# V6510_v3.net
KiCad netlist of a schematic drawn in EAGLE
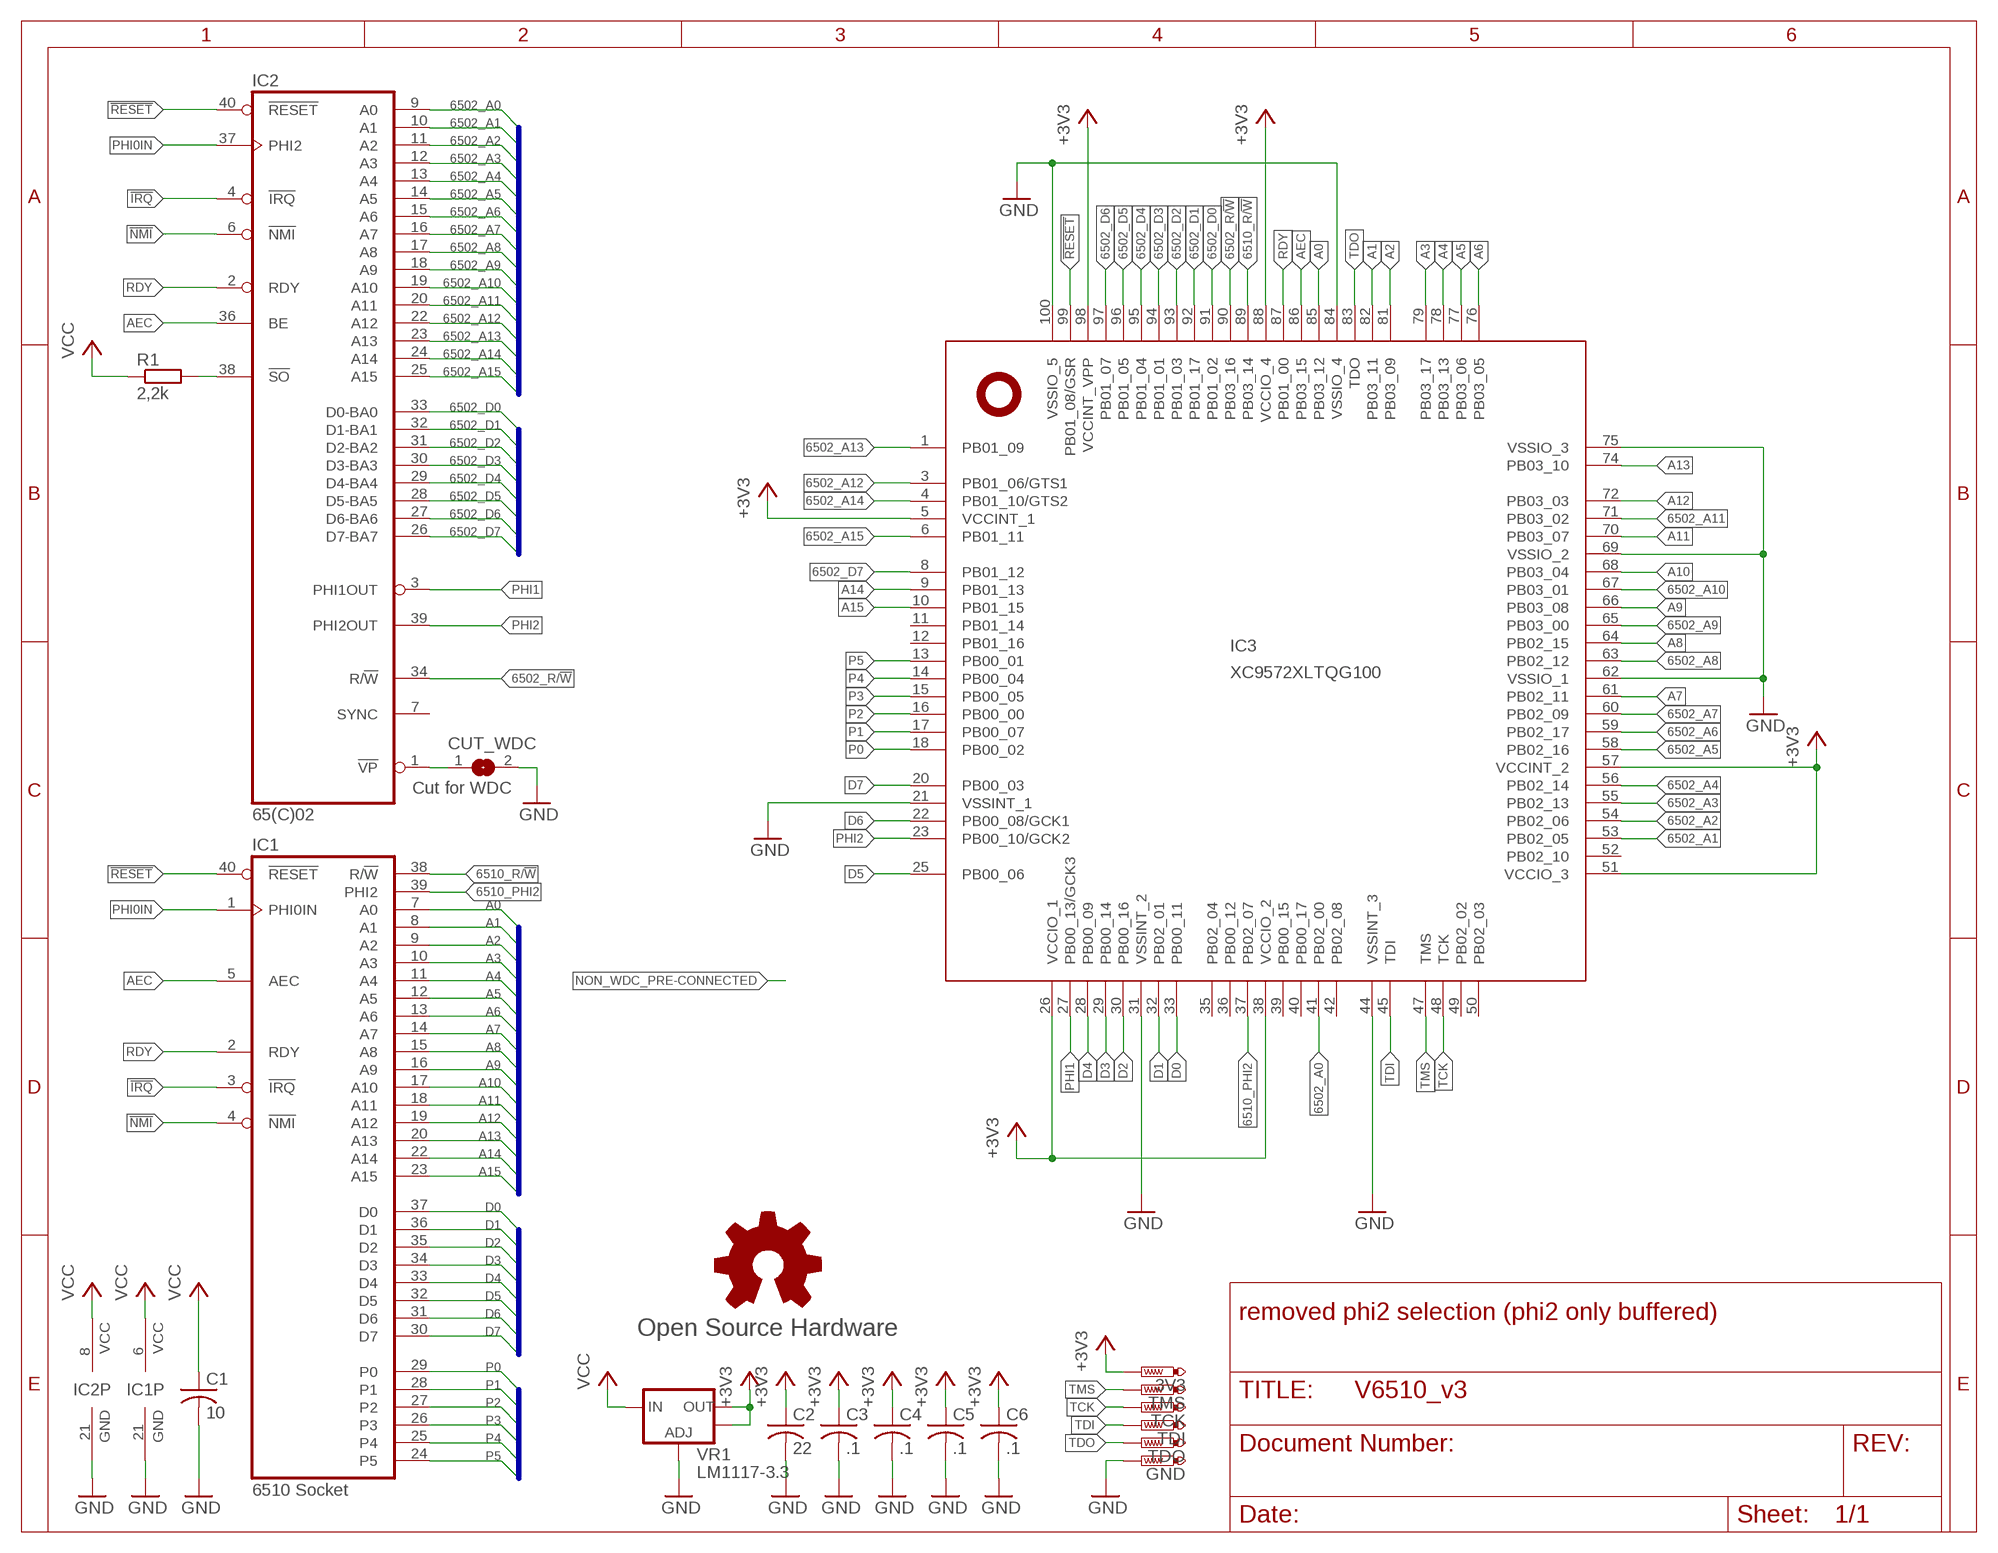
[diagram p0: schematic, sheet 1]

(export (version "E")
  (design (tool "Eeschema 10.0.6"))
  (components
    (comp (ref "3V3")
      (value "PTR1TP08R")
      (footprint "eagle-import:TP08R")
      (libsource (lib "eagle-import") (part "PTR1TP08R"))
    )
    (comp (ref "C1")
      (value "10")
      (footprint "eagle-import:C0805")
      (libsource (lib "eagle-import") (part "C-USC0805"))
    )
    (comp (ref "C2")
      (value "22")
      (footprint "eagle-import:C0805")
      (libsource (lib "eagle-import") (part "C-USC0805"))
    )
    (comp (ref "C3")
      (value ".1")
      (footprint "eagle-import:C0603")
      (libsource (lib "eagle-import") (part "C-USC0603"))
    )
    (comp (ref "C4")
      (value ".1")
      (footprint "eagle-import:C0603")
      (libsource (lib "eagle-import") (part "C-USC0603"))
    )
    (comp (ref "C5")
      (value ".1")
      (footprint "eagle-import:C0603")
      (libsource (lib "eagle-import") (part "C-USC0603"))
    )
    (comp (ref "C6")
      (value ".1")
      (footprint "eagle-import:C0603")
      (libsource (lib "eagle-import") (part "C-USC0603"))
    )
    (comp (ref "CUT_WDC")
      (value "Cut for WDC")
      (footprint "eagle-import:SJ")
      (libsource (lib "eagle-import") (part "SJ"))
    )
    (comp (ref "GND")
      (value "PTR1TP08R")
      (footprint "eagle-import:TP08R")
      (libsource (lib "eagle-import") (part "PTR1TP08R"))
    )
    (comp (ref "GOLD_ORB_SM1")
      (value "Open Source Hardware")
      (footprint "eagle-import:OSHW_5MM")
      (libsource (lib "eagle-import") (part "OSHWLOGOLOGO5MM"))
    )
    (comp (ref "IC1")
      (value "6510 Socket")
      (footprint "eagle-import:DIL40-ROUNDPAD")
      (libsource (lib "eagle-import") (part "6510"))
    )
    (comp (ref "IC2")
      (value "65(C)02")
      (footprint "eagle-import:DIL40-ROUNDPAD")
      (libsource (lib "eagle-import") (part "W65C02S-RP"))
    )
    (comp (ref "IC3")
      (value "XC9572XLTQG100")
      (footprint "eagle-import:TQFP100")
      (libsource (lib "eagle-import") (part "XC9572XLTQG100"))
    )
    (comp (ref "R1")
      (value "2,2k")
      (footprint "eagle-import:0603")
      (libsource (lib "eagle-import") (part "RESISTOR_0603"))
    )
    (comp (ref "TCK")
      (value "PTR1TP08R")
      (footprint "eagle-import:TP08R")
      (libsource (lib "eagle-import") (part "PTR1TP08R"))
    )
    (comp (ref "TDI")
      (value "PTR1TP08R")
      (footprint "eagle-import:TP08R")
      (libsource (lib "eagle-import") (part "PTR1TP08R"))
    )
    (comp (ref "TDO")
      (value "PTR1TP08R")
      (footprint "eagle-import:TP08R")
      (libsource (lib "eagle-import") (part "PTR1TP08R"))
    )
    (comp (ref "TMS")
      (value "PTR1TP08R")
      (footprint "eagle-import:TP08R")
      (libsource (lib "eagle-import") (part "PTR1TP08R"))
    )
    (comp (ref "VR1")
      (value "LM1117-3.3")
      (footprint "eagle-import:SOT223")
      (libsource (lib "eagle-import") (part "V_REG_LM1117SOT223"))
    )
  )
  (nets
    (net (code "1") (name "+3V3") (class "Default")
      (node (ref "3V3") (pin "TP") (pinfunction "TP_TP") (pintype "input"))
      (node (ref "C2") (pin "1") (pinfunction "1_1") (pintype "passive"))
      (node (ref "C3") (pin "1") (pinfunction "1_1") (pintype "passive"))
      (node (ref "C4") (pin "1") (pinfunction "1_1") (pintype "passive"))
      (node (ref "C5") (pin "1") (pinfunction "1_1") (pintype "passive"))
      (node (ref "C6") (pin "1") (pinfunction "1_1") (pintype "passive"))
      (node (ref "IC3") (pin "26") (pinfunction "VCCIO_1_26") (pintype "passive"))
      (node (ref "IC3") (pin "38") (pinfunction "VCCIO_2_38") (pintype "passive"))
      (node (ref "IC3") (pin "5") (pinfunction "VCCINT_1_5") (pintype "passive"))
      (node (ref "IC3") (pin "51") (pinfunction "VCCIO_3_51") (pintype "passive"))
      (node (ref "IC3") (pin "57") (pinfunction "VCCINT_2_57") (pintype "passive"))
      (node (ref "IC3") (pin "88") (pinfunction "VCCIO_4_88") (pintype "passive"))
      (node (ref "IC3") (pin "98") (pinfunction "VCCINT_VPP_98") (pintype "passive"))
      (node (ref "VR1") (pin "2") (pinfunction "OUT_2") (pintype "output"))
      (node (ref "VR1") (pin "4") (pinfunction "OUT_4") (pintype "output"))
    )
    (net (code "2") (name "/6502_R{slash}~{W}") (class "Default")
      (node (ref "IC2") (pin "34") (pinfunction "R/~{W}_34") (pintype "output"))
      (node (ref "IC3") (pin "90") (pinfunction "PB03_16_90") (pintype "bidirectional"))
    )
    (net (code "3") (name "/6510_R{slash}~{W}") (class "Default")
      (node (ref "IC1") (pin "38") (pinfunction "R/~{W}_38") (pintype "output"))
      (node (ref "IC3") (pin "89") (pinfunction "PB03_14_89") (pintype "bidirectional"))
    )
    (net (code "4") (name "/~{IRQ}") (class "Default")
      (node (ref "IC1") (pin "3") (pinfunction "~{IRQ}_3") (pintype "input"))
      (node (ref "IC2") (pin "4") (pinfunction "~{IRQ}_4") (pintype "input"))
    )
    (net (code "5") (name "/~{NMI}") (class "Default")
      (node (ref "IC1") (pin "4") (pinfunction "~{NMI}_4") (pintype "input"))
      (node (ref "IC2") (pin "6") (pinfunction "~{NMI}_6") (pintype "input"))
    )
    (net (code "6") (name "/~{RESET}") (class "Default")
      (node (ref "IC1") (pin "40") (pinfunction "~{RESET}_40") (pintype "input"))
      (node (ref "IC2") (pin "40") (pinfunction "~{RESET}_40") (pintype "input"))
      (node (ref "IC3") (pin "99") (pinfunction "PB01_08/GSR_99") (pintype "bidirectional"))
    )
    (net (code "7") (name "6502_A0") (class "Default")
      (node (ref "IC2") (pin "9") (pinfunction "A0_9") (pintype "tri_state"))
      (node (ref "IC3") (pin "41") (pinfunction "PB02_00_41") (pintype "bidirectional"))
    )
    (net (code "8") (name "6502_A1") (class "Default")
      (node (ref "IC2") (pin "10") (pinfunction "A1_10") (pintype "tri_state"))
      (node (ref "IC3") (pin "53") (pinfunction "PB02_05_53") (pintype "bidirectional"))
    )
    (net (code "9") (name "6502_A2") (class "Default")
      (node (ref "IC2") (pin "11") (pinfunction "A2_11") (pintype "tri_state"))
      (node (ref "IC3") (pin "54") (pinfunction "PB02_06_54") (pintype "bidirectional"))
    )
    (net (code "10") (name "6502_A3") (class "Default")
      (node (ref "IC2") (pin "12") (pinfunction "A3_12") (pintype "tri_state"))
      (node (ref "IC3") (pin "55") (pinfunction "PB02_13_55") (pintype "bidirectional"))
    )
    (net (code "11") (name "6502_A4") (class "Default")
      (node (ref "IC2") (pin "13") (pinfunction "A4_13") (pintype "tri_state"))
      (node (ref "IC3") (pin "56") (pinfunction "PB02_14_56") (pintype "bidirectional"))
    )
    (net (code "12") (name "6502_A5") (class "Default")
      (node (ref "IC2") (pin "14") (pinfunction "A5_14") (pintype "tri_state"))
      (node (ref "IC3") (pin "58") (pinfunction "PB02_16_58") (pintype "bidirectional"))
    )
    (net (code "13") (name "6502_A6") (class "Default")
      (node (ref "IC2") (pin "15") (pinfunction "A6_15") (pintype "tri_state"))
      (node (ref "IC3") (pin "59") (pinfunction "PB02_17_59") (pintype "bidirectional"))
    )
    (net (code "14") (name "6502_A7") (class "Default")
      (node (ref "IC2") (pin "16") (pinfunction "A7_16") (pintype "tri_state"))
      (node (ref "IC3") (pin "60") (pinfunction "PB02_09_60") (pintype "bidirectional"))
    )
    (net (code "15") (name "6502_A8") (class "Default")
      (node (ref "IC2") (pin "17") (pinfunction "A8_17") (pintype "tri_state"))
      (node (ref "IC3") (pin "63") (pinfunction "PB02_12_63") (pintype "bidirectional"))
    )
    (net (code "16") (name "6502_A9") (class "Default")
      (node (ref "IC2") (pin "18") (pinfunction "A9_18") (pintype "tri_state"))
      (node (ref "IC3") (pin "65") (pinfunction "PB03_00_65") (pintype "bidirectional"))
    )
    (net (code "17") (name "6502_A10") (class "Default")
      (node (ref "IC2") (pin "19") (pinfunction "A10_19") (pintype "tri_state"))
      (node (ref "IC3") (pin "67") (pinfunction "PB03_01_67") (pintype "bidirectional"))
    )
    (net (code "18") (name "6502_A11") (class "Default")
      (node (ref "IC2") (pin "20") (pinfunction "A11_20") (pintype "tri_state"))
      (node (ref "IC3") (pin "71") (pinfunction "PB03_02_71") (pintype "bidirectional"))
    )
    (net (code "19") (name "6502_A12") (class "Default")
      (node (ref "IC2") (pin "22") (pinfunction "A12_22") (pintype "tri_state"))
      (node (ref "IC3") (pin "3") (pinfunction "PB01_06/GTS1_3") (pintype "bidirectional"))
    )
    (net (code "20") (name "6502_A13") (class "Default")
      (node (ref "IC2") (pin "23") (pinfunction "A13_23") (pintype "tri_state"))
      (node (ref "IC3") (pin "1") (pinfunction "PB01_09_1") (pintype "bidirectional"))
    )
    (net (code "21") (name "6502_A14") (class "Default")
      (node (ref "IC2") (pin "24") (pinfunction "A14_24") (pintype "tri_state"))
      (node (ref "IC3") (pin "4") (pinfunction "PB01_10/GTS2_4") (pintype "bidirectional"))
    )
    (net (code "22") (name "6502_A15") (class "Default")
      (node (ref "IC2") (pin "25") (pinfunction "A15_25") (pintype "tri_state"))
      (node (ref "IC3") (pin "6") (pinfunction "PB01_11_6") (pintype "bidirectional"))
    )
    (net (code "23") (name "6502_D0") (class "Default")
      (node (ref "IC2") (pin "33") (pinfunction "D0-BA0_33") (pintype "bidirectional"))
      (node (ref "IC3") (pin "91") (pinfunction "PB01_02_91") (pintype "bidirectional"))
    )
    (net (code "24") (name "6502_D1") (class "Default")
      (node (ref "IC2") (pin "32") (pinfunction "D1-BA1_32") (pintype "bidirectional"))
      (node (ref "IC3") (pin "92") (pinfunction "PB01_17_92") (pintype "bidirectional"))
    )
    (net (code "25") (name "6502_D2") (class "Default")
      (node (ref "IC2") (pin "31") (pinfunction "D2-BA2_31") (pintype "bidirectional"))
      (node (ref "IC3") (pin "93") (pinfunction "PB01_03_93") (pintype "bidirectional"))
    )
    (net (code "26") (name "6502_D3") (class "Default")
      (node (ref "IC2") (pin "30") (pinfunction "D3-BA3_30") (pintype "bidirectional"))
      (node (ref "IC3") (pin "94") (pinfunction "PB01_01_94") (pintype "bidirectional"))
    )
    (net (code "27") (name "6502_D4") (class "Default")
      (node (ref "IC2") (pin "29") (pinfunction "D4-BA4_29") (pintype "bidirectional"))
      (node (ref "IC3") (pin "95") (pinfunction "PB01_04_95") (pintype "bidirectional"))
    )
    (net (code "28") (name "6502_D5") (class "Default")
      (node (ref "IC2") (pin "28") (pinfunction "D5-BA5_28") (pintype "bidirectional"))
      (node (ref "IC3") (pin "96") (pinfunction "PB01_05_96") (pintype "bidirectional"))
    )
    (net (code "29") (name "6502_D6") (class "Default")
      (node (ref "IC2") (pin "27") (pinfunction "D6-BA6_27") (pintype "bidirectional"))
      (node (ref "IC3") (pin "97") (pinfunction "PB01_07_97") (pintype "bidirectional"))
    )
    (net (code "30") (name "6502_D7") (class "Default")
      (node (ref "IC2") (pin "26") (pinfunction "D7-BA7_26") (pintype "bidirectional"))
      (node (ref "IC3") (pin "8") (pinfunction "PB01_12_8") (pintype "bidirectional"))
    )
    (net (code "31") (name "6510_PHI2") (class "Default")
      (node (ref "IC1") (pin "39") (pinfunction "PHI2_39") (pintype "output"))
      (node (ref "IC3") (pin "37") (pinfunction "PB02_07_37") (pintype "bidirectional"))
    )
    (net (code "32") (name "A0") (class "Default")
      (node (ref "IC1") (pin "7") (pinfunction "A0_7") (pintype "output"))
      (node (ref "IC3") (pin "85") (pinfunction "PB03_12_85") (pintype "bidirectional"))
    )
    (net (code "33") (name "A1") (class "Default")
      (node (ref "IC1") (pin "8") (pinfunction "A1_8") (pintype "output"))
      (node (ref "IC3") (pin "82") (pinfunction "PB03_11_82") (pintype "bidirectional"))
    )
    (net (code "34") (name "A2") (class "Default")
      (node (ref "IC1") (pin "9") (pinfunction "A2_9") (pintype "output"))
      (node (ref "IC3") (pin "81") (pinfunction "PB03_09_81") (pintype "bidirectional"))
    )
    (net (code "35") (name "A3") (class "Default")
      (node (ref "IC1") (pin "10") (pinfunction "A3_10") (pintype "output"))
      (node (ref "IC3") (pin "79") (pinfunction "PB03_17_79") (pintype "bidirectional"))
    )
    (net (code "36") (name "A4") (class "Default")
      (node (ref "IC1") (pin "11") (pinfunction "A4_11") (pintype "output"))
      (node (ref "IC3") (pin "78") (pinfunction "PB03_13_78") (pintype "bidirectional"))
    )
    (net (code "37") (name "A5") (class "Default")
      (node (ref "IC1") (pin "12") (pinfunction "A5_12") (pintype "output"))
      (node (ref "IC3") (pin "77") (pinfunction "PB03_06_77") (pintype "bidirectional"))
    )
    (net (code "38") (name "A6") (class "Default")
      (node (ref "IC1") (pin "13") (pinfunction "A6_13") (pintype "output"))
      (node (ref "IC3") (pin "76") (pinfunction "PB03_05_76") (pintype "bidirectional"))
    )
    (net (code "39") (name "A7") (class "Default")
      (node (ref "IC1") (pin "14") (pinfunction "A7_14") (pintype "output"))
      (node (ref "IC3") (pin "61") (pinfunction "PB02_11_61") (pintype "bidirectional"))
    )
    (net (code "40") (name "A8") (class "Default")
      (node (ref "IC1") (pin "15") (pinfunction "A8_15") (pintype "output"))
      (node (ref "IC3") (pin "64") (pinfunction "PB02_15_64") (pintype "bidirectional"))
    )
    (net (code "41") (name "A9") (class "Default")
      (node (ref "IC1") (pin "16") (pinfunction "A9_16") (pintype "output"))
      (node (ref "IC3") (pin "66") (pinfunction "PB03_08_66") (pintype "bidirectional"))
    )
    (net (code "42") (name "A10") (class "Default")
      (node (ref "IC1") (pin "17") (pinfunction "A10_17") (pintype "output"))
      (node (ref "IC3") (pin "68") (pinfunction "PB03_04_68") (pintype "bidirectional"))
    )
    (net (code "43") (name "A11") (class "Default")
      (node (ref "IC1") (pin "18") (pinfunction "A11_18") (pintype "output"))
      (node (ref "IC3") (pin "70") (pinfunction "PB03_07_70") (pintype "bidirectional"))
    )
    (net (code "44") (name "A12") (class "Default")
      (node (ref "IC1") (pin "19") (pinfunction "A12_19") (pintype "output"))
      (node (ref "IC3") (pin "72") (pinfunction "PB03_03_72") (pintype "bidirectional"))
    )
    (net (code "45") (name "A13") (class "Default")
      (node (ref "IC1") (pin "20") (pinfunction "A13_20") (pintype "output"))
      (node (ref "IC3") (pin "74") (pinfunction "PB03_10_74") (pintype "bidirectional"))
    )
    (net (code "46") (name "A14") (class "Default")
      (node (ref "IC1") (pin "22") (pinfunction "A14_22") (pintype "output"))
      (node (ref "IC3") (pin "9") (pinfunction "PB01_13_9") (pintype "bidirectional"))
    )
    (net (code "47") (name "A15") (class "Default")
      (node (ref "IC1") (pin "23") (pinfunction "A15_23") (pintype "output"))
      (node (ref "IC3") (pin "10") (pinfunction "PB01_15_10") (pintype "bidirectional"))
    )
    (net (code "48") (name "AEC") (class "Default")
      (node (ref "IC1") (pin "5") (pinfunction "AEC_5") (pintype "input"))
      (node (ref "IC2") (pin "36") (pinfunction "BE_36") (pintype "input"))
      (node (ref "IC3") (pin "86") (pinfunction "PB03_15_86") (pintype "bidirectional"))
    )
    (net (code "49") (name "D0") (class "Default")
      (node (ref "IC1") (pin "37") (pinfunction "D0_37") (pintype "bidirectional"))
      (node (ref "IC3") (pin "33") (pinfunction "PB00_11_33") (pintype "bidirectional"))
    )
    (net (code "50") (name "D1") (class "Default")
      (node (ref "IC1") (pin "36") (pinfunction "D1_36") (pintype "bidirectional"))
      (node (ref "IC3") (pin "32") (pinfunction "PB02_01_32") (pintype "bidirectional"))
    )
    (net (code "51") (name "D2") (class "Default")
      (node (ref "IC1") (pin "35") (pinfunction "D2_35") (pintype "bidirectional"))
      (node (ref "IC3") (pin "30") (pinfunction "PB00_16_30") (pintype "bidirectional"))
    )
    (net (code "52") (name "D3") (class "Default")
      (node (ref "IC1") (pin "34") (pinfunction "D3_34") (pintype "bidirectional"))
      (node (ref "IC3") (pin "29") (pinfunction "PB00_14_29") (pintype "bidirectional"))
    )
    (net (code "53") (name "D4") (class "Default")
      (node (ref "IC1") (pin "33") (pinfunction "D4_33") (pintype "bidirectional"))
      (node (ref "IC3") (pin "28") (pinfunction "PB00_09_28") (pintype "bidirectional"))
    )
    (net (code "54") (name "D5") (class "Default")
      (node (ref "IC1") (pin "32") (pinfunction "D5_32") (pintype "bidirectional"))
      (node (ref "IC3") (pin "25") (pinfunction "PB00_06_25") (pintype "bidirectional"))
    )
    (net (code "55") (name "D6") (class "Default")
      (node (ref "IC1") (pin "31") (pinfunction "D6_31") (pintype "bidirectional"))
      (node (ref "IC3") (pin "22") (pinfunction "PB00_08/GCK1_22") (pintype "bidirectional"))
    )
    (net (code "56") (name "D7") (class "Default")
      (node (ref "IC1") (pin "30") (pinfunction "D7_30") (pintype "bidirectional"))
      (node (ref "IC3") (pin "20") (pinfunction "PB00_03_20") (pintype "bidirectional"))
    )
    (net (code "57") (name "GND") (class "Default")
      (node (ref "C1") (pin "2") (pinfunction "2_2") (pintype "passive"))
      (node (ref "C2") (pin "2") (pinfunction "2_2") (pintype "passive"))
      (node (ref "C3") (pin "2") (pinfunction "2_2") (pintype "passive"))
      (node (ref "C4") (pin "2") (pinfunction "2_2") (pintype "passive"))
      (node (ref "C5") (pin "2") (pinfunction "2_2") (pintype "passive"))
      (node (ref "C6") (pin "2") (pinfunction "2_2") (pintype "passive"))
      (node (ref "CUT_WDC") (pin "2") (pinfunction "2_2") (pintype "passive"))
      (node (ref "GND") (pin "TP") (pinfunction "TP_TP") (pintype "input"))
      (node (ref "IC1") (pin "21") (pinfunction "GND_21") (pintype "power_in"))
      (node (ref "IC2") (pin "21") (pinfunction "GND_21") (pintype "power_in"))
      (node (ref "IC3") (pin "100") (pinfunction "VSSIO_5_100") (pintype "passive"))
      (node (ref "IC3") (pin "21") (pinfunction "VSSINT_1_21") (pintype "passive"))
      (node (ref "IC3") (pin "31") (pinfunction "VSSINT_2_31") (pintype "passive"))
      (node (ref "IC3") (pin "44") (pinfunction "VSSINT_3_44") (pintype "passive"))
      (node (ref "IC3") (pin "62") (pinfunction "VSSIO_1_62") (pintype "passive"))
      (node (ref "IC3") (pin "69") (pinfunction "VSSIO_2_69") (pintype "passive"))
      (node (ref "IC3") (pin "75") (pinfunction "VSSIO_3_75") (pintype "passive"))
      (node (ref "IC3") (pin "84") (pinfunction "VSSIO_4_84") (pintype "passive"))
      (node (ref "VR1") (pin "1") (pinfunction "ADJ_1") (pintype "input"))
    )
    (net (code "59") (name "Net-(IC2A-~{SO})") (class "Default")
      (node (ref "IC2") (pin "38") (pinfunction "~{SO}_38") (pintype "output"))
      (node (ref "R1") (pin "2") (pinfunction "2_2") (pintype "passive"))
    )
    (net (code "60") (name "Net-(IC2A-~{VP})") (class "Default")
      (node (ref "CUT_WDC") (pin "1") (pinfunction "1_1") (pintype "passive"))
      (node (ref "IC2") (pin "1") (pinfunction "~{VP}_1") (pintype "output"))
    )
    (net (code "61") (name "P0") (class "Default")
      (node (ref "IC1") (pin "29") (pinfunction "P0_29") (pintype "output"))
      (node (ref "IC3") (pin "18") (pinfunction "PB00_02_18") (pintype "bidirectional"))
    )
    (net (code "62") (name "P1") (class "Default")
      (node (ref "IC1") (pin "28") (pinfunction "P1_28") (pintype "output"))
      (node (ref "IC3") (pin "17") (pinfunction "PB00_07_17") (pintype "bidirectional"))
    )
    (net (code "63") (name "P2") (class "Default")
      (node (ref "IC1") (pin "27") (pinfunction "P2_27") (pintype "output"))
      (node (ref "IC3") (pin "16") (pinfunction "PB00_00_16") (pintype "bidirectional"))
    )
    (net (code "64") (name "P3") (class "Default")
      (node (ref "IC1") (pin "26") (pinfunction "P3_26") (pintype "output"))
      (node (ref "IC3") (pin "15") (pinfunction "PB00_05_15") (pintype "bidirectional"))
    )
    (net (code "65") (name "P4") (class "Default")
      (node (ref "IC1") (pin "25") (pinfunction "P4_25") (pintype "output"))
      (node (ref "IC3") (pin "14") (pinfunction "PB00_04_14") (pintype "bidirectional"))
    )
    (net (code "66") (name "P5") (class "Default")
      (node (ref "IC1") (pin "24") (pinfunction "P5_24") (pintype "output"))
      (node (ref "IC3") (pin "13") (pinfunction "PB00_01_13") (pintype "bidirectional"))
    )
    (net (code "67") (name "PHI0IN") (class "Default")
      (node (ref "IC1") (pin "1") (pinfunction "PHI0IN_1") (pintype "input"))
      (node (ref "IC2") (pin "37") (pinfunction "PHI2_37") (pintype "input"))
    )
    (net (code "68") (name "PHI1") (class "Default")
      (node (ref "IC2") (pin "3") (pinfunction "PHI1OUT_3") (pintype "input"))
      (node (ref "IC3") (pin "27") (pinfunction "PB00_13/GCK3_27") (pintype "bidirectional"))
    )
    (net (code "69") (name "PHI2") (class "Default")
      (node (ref "IC2") (pin "39") (pinfunction "PHI2OUT_39") (pintype "output"))
      (node (ref "IC3") (pin "23") (pinfunction "PB00_10/GCK2_23") (pintype "bidirectional"))
    )
    (net (code "70") (name "RDY") (class "Default")
      (node (ref "IC1") (pin "2") (pinfunction "RDY_2") (pintype "input"))
      (node (ref "IC2") (pin "2") (pinfunction "RDY_2") (pintype "bidirectional"))
      (node (ref "IC3") (pin "87") (pinfunction "PB01_00_87") (pintype "bidirectional"))
    )
    (net (code "71") (name "TCK") (class "Default")
      (node (ref "IC3") (pin "48") (pinfunction "TCK_48") (pintype "input"))
      (node (ref "TCK") (pin "TP") (pinfunction "TP_TP") (pintype "input"))
    )
    (net (code "72") (name "TDI") (class "Default")
      (node (ref "IC3") (pin "45") (pinfunction "TDI_45") (pintype "input"))
      (node (ref "TDI") (pin "TP") (pinfunction "TP_TP") (pintype "input"))
    )
    (net (code "73") (name "TDO") (class "Default")
      (node (ref "IC3") (pin "83") (pinfunction "TDO_83") (pintype "output"))
      (node (ref "TDO") (pin "TP") (pinfunction "TP_TP") (pintype "input"))
    )
    (net (code "74") (name "TMS") (class "Default")
      (node (ref "IC3") (pin "47") (pinfunction "TMS_47") (pintype "input"))
      (node (ref "TMS") (pin "TP") (pinfunction "TP_TP") (pintype "input"))
    )
    (net (code "75") (name "VCC") (class "Default")
      (node (ref "C1") (pin "1") (pinfunction "1_1") (pintype "passive"))
      (node (ref "IC1") (pin "6") (pinfunction "VCC_6") (pintype "power_in"))
      (node (ref "IC2") (pin "8") (pinfunction "VCC_8") (pintype "power_in"))
      (node (ref "R1") (pin "1") (pinfunction "1_1") (pintype "passive"))
      (node (ref "VR1") (pin "3") (pinfunction "IN_3") (pintype "input"))
    )
    (net (code "76") (name "unconnected-(IC2A-SYNC-Pad7)") (class "Default")
      (node (ref "IC2") (pin "7") (pinfunction "SYNC_7") (pintype "output"))
    )
    (net (code "77") (name "unconnected-(IC3-PB00_12-Pad36)") (class "Default")
      (node (ref "IC3") (pin "36") (pinfunction "PB00_12_36") (pintype "bidirectional"))
    )
    (net (code "78") (name "unconnected-(IC3-PB00_15-Pad39)") (class "Default")
      (node (ref "IC3") (pin "39") (pinfunction "PB00_15_39") (pintype "bidirectional"))
    )
    (net (code "79") (name "unconnected-(IC3-PB00_17-Pad40)") (class "Default")
      (node (ref "IC3") (pin "40") (pinfunction "PB00_17_40") (pintype "bidirectional"))
    )
    (net (code "80") (name "unconnected-(IC3-PB01_14-Pad11)") (class "Default")
      (node (ref "IC3") (pin "11") (pinfunction "PB01_14_11") (pintype "bidirectional"))
    )
    (net (code "81") (name "unconnected-(IC3-PB01_16-Pad12)") (class "Default")
      (node (ref "IC3") (pin "12") (pinfunction "PB01_16_12") (pintype "bidirectional"))
    )
    (net (code "82") (name "unconnected-(IC3-PB02_02-Pad49)") (class "Default")
      (node (ref "IC3") (pin "49") (pinfunction "PB02_02_49") (pintype "bidirectional"))
    )
    (net (code "83") (name "unconnected-(IC3-PB02_03-Pad50)") (class "Default")
      (node (ref "IC3") (pin "50") (pinfunction "PB02_03_50") (pintype "bidirectional"))
    )
    (net (code "84") (name "unconnected-(IC3-PB02_04-Pad35)") (class "Default")
      (node (ref "IC3") (pin "35") (pinfunction "PB02_04_35") (pintype "bidirectional"))
    )
    (net (code "85") (name "unconnected-(IC3-PB02_08-Pad42)") (class "Default")
      (node (ref "IC3") (pin "42") (pinfunction "PB02_08_42") (pintype "bidirectional"))
    )
    (net (code "86") (name "unconnected-(IC3-PB02_10-Pad52)") (class "Default")
      (node (ref "IC3") (pin "52") (pinfunction "PB02_10_52") (pintype "bidirectional"))
    )
  )
)
